# dice.net
KiCad netlist of a schematic drawn in EAGLE
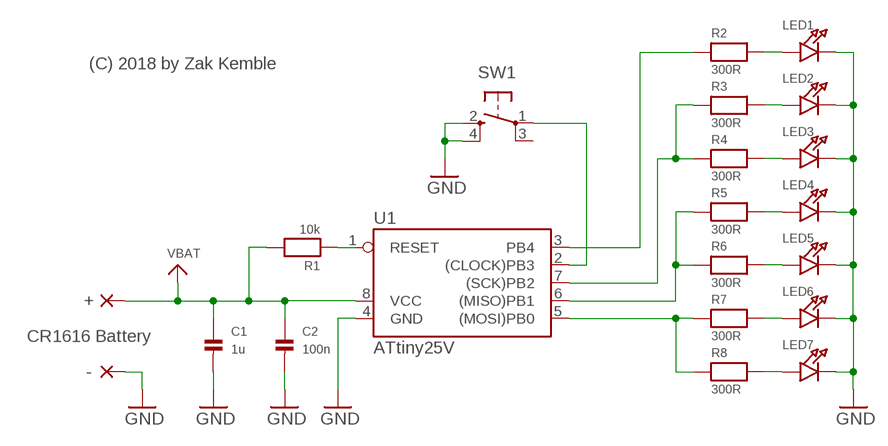
[diagram p0: schematic, sheet 1]

(export (version "E")
  (design (tool "Eeschema 10.0.6"))
  (components
    (comp (ref "C1")
      (value "1u")
      (footprint "eagle-import:0402")
      (libsource (lib "eagle-import") (part "CAP_CERAMIC0402"))
    )
    (comp (ref "C2")
      (value "100n")
      (footprint "eagle-import:0402")
      (libsource (lib "eagle-import") (part "CAP_CERAMIC0402"))
    )
    (comp (ref "LED1")
      (value "LED0603_NOOUTLINE")
      (footprint "eagle-import:CHIPLED_0603_NOOUTLINE")
      (libsource (lib "eagle-import") (part "LED0603_NOOUTLINE"))
    )
    (comp (ref "LED2")
      (value "LED0603_NOOUTLINE")
      (footprint "eagle-import:CHIPLED_0603_NOOUTLINE")
      (libsource (lib "eagle-import") (part "LED0603_NOOUTLINE"))
    )
    (comp (ref "LED3")
      (value "LED0603_NOOUTLINE")
      (footprint "eagle-import:CHIPLED_0603_NOOUTLINE")
      (libsource (lib "eagle-import") (part "LED0603_NOOUTLINE"))
    )
    (comp (ref "LED4")
      (value "LED0603_NOOUTLINE")
      (footprint "eagle-import:CHIPLED_0603_NOOUTLINE")
      (libsource (lib "eagle-import") (part "LED0603_NOOUTLINE"))
    )
    (comp (ref "LED5")
      (value "LED0603_NOOUTLINE")
      (footprint "eagle-import:CHIPLED_0603_NOOUTLINE")
      (libsource (lib "eagle-import") (part "LED0603_NOOUTLINE"))
    )
    (comp (ref "LED6")
      (value "LED0603_NOOUTLINE")
      (footprint "eagle-import:CHIPLED_0603_NOOUTLINE")
      (libsource (lib "eagle-import") (part "LED0603_NOOUTLINE"))
    )
    (comp (ref "LED7")
      (value "LED0603_NOOUTLINE")
      (footprint "eagle-import:CHIPLED_0603_NOOUTLINE")
      (libsource (lib "eagle-import") (part "LED0603_NOOUTLINE"))
    )
    (comp (ref "PAD1")
      (value "PADSMD-2X3")
      (footprint "eagle-import:PAD-SMD-2X3")
      (libsource (lib "eagle-import") (part "PADSMD-2X3"))
    )
    (comp (ref "PAD2")
      (value "PADSMD-2X3")
      (footprint "eagle-import:PAD-SMD-2X3")
      (libsource (lib "eagle-import") (part "PADSMD-2X3"))
    )
    (comp (ref "R1")
      (value "10k")
      (footprint "eagle-import:0402")
      (libsource (lib "eagle-import") (part "RESISTOR0402"))
    )
    (comp (ref "R2")
      (value "300R")
      (footprint "eagle-import:0402")
      (libsource (lib "eagle-import") (part "RESISTOR0402"))
    )
    (comp (ref "R3")
      (value "300R")
      (footprint "eagle-import:0402")
      (libsource (lib "eagle-import") (part "RESISTOR0402"))
    )
    (comp (ref "R4")
      (value "300R")
      (footprint "eagle-import:0402")
      (libsource (lib "eagle-import") (part "RESISTOR0402"))
    )
    (comp (ref "R5")
      (value "300R")
      (footprint "eagle-import:0402")
      (libsource (lib "eagle-import") (part "RESISTOR0402"))
    )
    (comp (ref "R6")
      (value "300R")
      (footprint "eagle-import:0402")
      (libsource (lib "eagle-import") (part "RESISTOR0402"))
    )
    (comp (ref "R7")
      (value "300R")
      (footprint "eagle-import:0402")
      (libsource (lib "eagle-import") (part "RESISTOR0402"))
    )
    (comp (ref "R8")
      (value "300R")
      (footprint "eagle-import:0402")
      (libsource (lib "eagle-import") (part "RESISTOR0402"))
    )
    (comp (ref "SW1")
      (value "SPST_TACTRA")
      (footprint "eagle-import:TACT_SMD2")
      (libsource (lib "eagle-import") (part "SPST_TACTRA"))
    )
    (comp (ref "U1")
      (value "ATtiny25V")
      (footprint "eagle-import:SOIC8_150MIL_SMPAD")
      (libsource (lib "eagle-import") (part "ATTINY85150MIL_SMPAD"))
    )
  )
  (nets
    (net (code "1") (name "GND") (class "Default")
      (node (ref "C1") (pin "2") (pinfunction "P$2_2") (pintype "passive"))
      (node (ref "C2") (pin "2") (pinfunction "P$2_2") (pintype "passive"))
      (node (ref "LED1") (pin "C") (pinfunction "C_C") (pintype "passive"))
      (node (ref "LED2") (pin "C") (pinfunction "C_C") (pintype "passive"))
      (node (ref "LED3") (pin "C") (pinfunction "C_C") (pintype "passive"))
      (node (ref "LED4") (pin "C") (pinfunction "C_C") (pintype "passive"))
      (node (ref "LED5") (pin "C") (pinfunction "C_C") (pintype "passive"))
      (node (ref "LED6") (pin "C") (pinfunction "C_C") (pintype "passive"))
      (node (ref "LED7") (pin "C") (pinfunction "C_C") (pintype "passive"))
      (node (ref "PAD2") (pin "1") (pinfunction "P$1_1") (pintype "passive"))
      (node (ref "SW1") (pin "2") (pinfunction "S_2") (pintype "passive"))
      (node (ref "SW1") (pin "4") (pinfunction "S1_4") (pintype "passive"))
      (node (ref "U1") (pin "4") (pinfunction "GND_4") (pintype "power_in"))
    )
    (net (code "2") (name "Net-(LED1-PadA)") (class "Default")
      (node (ref "LED1") (pin "A") (pinfunction "A_A") (pintype "passive"))
      (node (ref "R2") (pin "2") (pinfunction "2_2") (pintype "passive"))
    )
    (net (code "3") (name "Net-(LED2-PadA)") (class "Default")
      (node (ref "LED2") (pin "A") (pinfunction "A_A") (pintype "passive"))
      (node (ref "R3") (pin "2") (pinfunction "2_2") (pintype "passive"))
    )
    (net (code "4") (name "Net-(LED3-PadA)") (class "Default")
      (node (ref "LED3") (pin "A") (pinfunction "A_A") (pintype "passive"))
      (node (ref "R4") (pin "2") (pinfunction "2_2") (pintype "passive"))
    )
    (net (code "5") (name "Net-(LED4-PadA)") (class "Default")
      (node (ref "LED4") (pin "A") (pinfunction "A_A") (pintype "passive"))
      (node (ref "R5") (pin "2") (pinfunction "2_2") (pintype "passive"))
    )
    (net (code "6") (name "Net-(LED5-PadA)") (class "Default")
      (node (ref "LED5") (pin "A") (pinfunction "A_A") (pintype "passive"))
      (node (ref "R6") (pin "2") (pinfunction "2_2") (pintype "passive"))
    )
    (net (code "7") (name "Net-(LED6-PadA)") (class "Default")
      (node (ref "LED6") (pin "A") (pinfunction "A_A") (pintype "passive"))
      (node (ref "R7") (pin "2") (pinfunction "2_2") (pintype "passive"))
    )
    (net (code "8") (name "Net-(LED7-PadA)") (class "Default")
      (node (ref "LED7") (pin "A") (pinfunction "A_A") (pintype "passive"))
      (node (ref "R8") (pin "2") (pinfunction "2_2") (pintype "passive"))
    )
    (net (code "9") (name "Net-(SW1-P)") (class "Default")
      (node (ref "SW1") (pin "1") (pinfunction "P_1") (pintype "passive"))
      (node (ref "U1") (pin "2") (pinfunction "(CLOCK)PB3_2") (pintype "bidirectional"))
    )
    (net (code "10") (name "Net-(U1-(MISO)PB1)") (class "Default")
      (node (ref "R5") (pin "1") (pinfunction "1_1") (pintype "passive"))
      (node (ref "R6") (pin "1") (pinfunction "1_1") (pintype "passive"))
      (node (ref "U1") (pin "6") (pinfunction "(MISO)PB1_6") (pintype "bidirectional"))
    )
    (net (code "11") (name "Net-(U1-(MOSI)PB0)") (class "Default")
      (node (ref "R7") (pin "1") (pinfunction "1_1") (pintype "passive"))
      (node (ref "R8") (pin "1") (pinfunction "1_1") (pintype "passive"))
      (node (ref "U1") (pin "5") (pinfunction "(MOSI)PB0_5") (pintype "bidirectional"))
    )
    (net (code "12") (name "Net-(U1-(SCK)PB2)") (class "Default")
      (node (ref "R3") (pin "1") (pinfunction "1_1") (pintype "passive"))
      (node (ref "R4") (pin "1") (pinfunction "1_1") (pintype "passive"))
      (node (ref "U1") (pin "7") (pinfunction "(SCK)PB2_7") (pintype "bidirectional"))
    )
    (net (code "13") (name "Net-(U1-PB4)") (class "Default")
      (node (ref "R2") (pin "1") (pinfunction "1_1") (pintype "passive"))
      (node (ref "U1") (pin "3") (pinfunction "PB4_3") (pintype "bidirectional"))
    )
    (net (code "14") (name "Net-(U1-RESET)") (class "Default")
      (node (ref "R1") (pin "1") (pinfunction "1_1") (pintype "passive"))
      (node (ref "U1") (pin "1") (pinfunction "RESET_1") (pintype "input"))
    )
    (net (code "15") (name "VBAT") (class "Default")
      (node (ref "C1") (pin "1") (pinfunction "P$1_1") (pintype "passive"))
      (node (ref "C2") (pin "1") (pinfunction "P$1_1") (pintype "passive"))
      (node (ref "PAD1") (pin "1") (pinfunction "P$1_1") (pintype "passive"))
      (node (ref "R1") (pin "2") (pinfunction "2_2") (pintype "passive"))
      (node (ref "U1") (pin "8") (pinfunction "VCC_8") (pintype "power_in"))
    )
    (net (code "16") (name "unconnected-(SW1-P1-Pad3)") (class "Default")
      (node (ref "SW1") (pin "3") (pinfunction "P1_3") (pintype "passive"))
    )
  )
)
